# Sheet1.net
KiCad netlist of a schematic drawn in Altium Designer
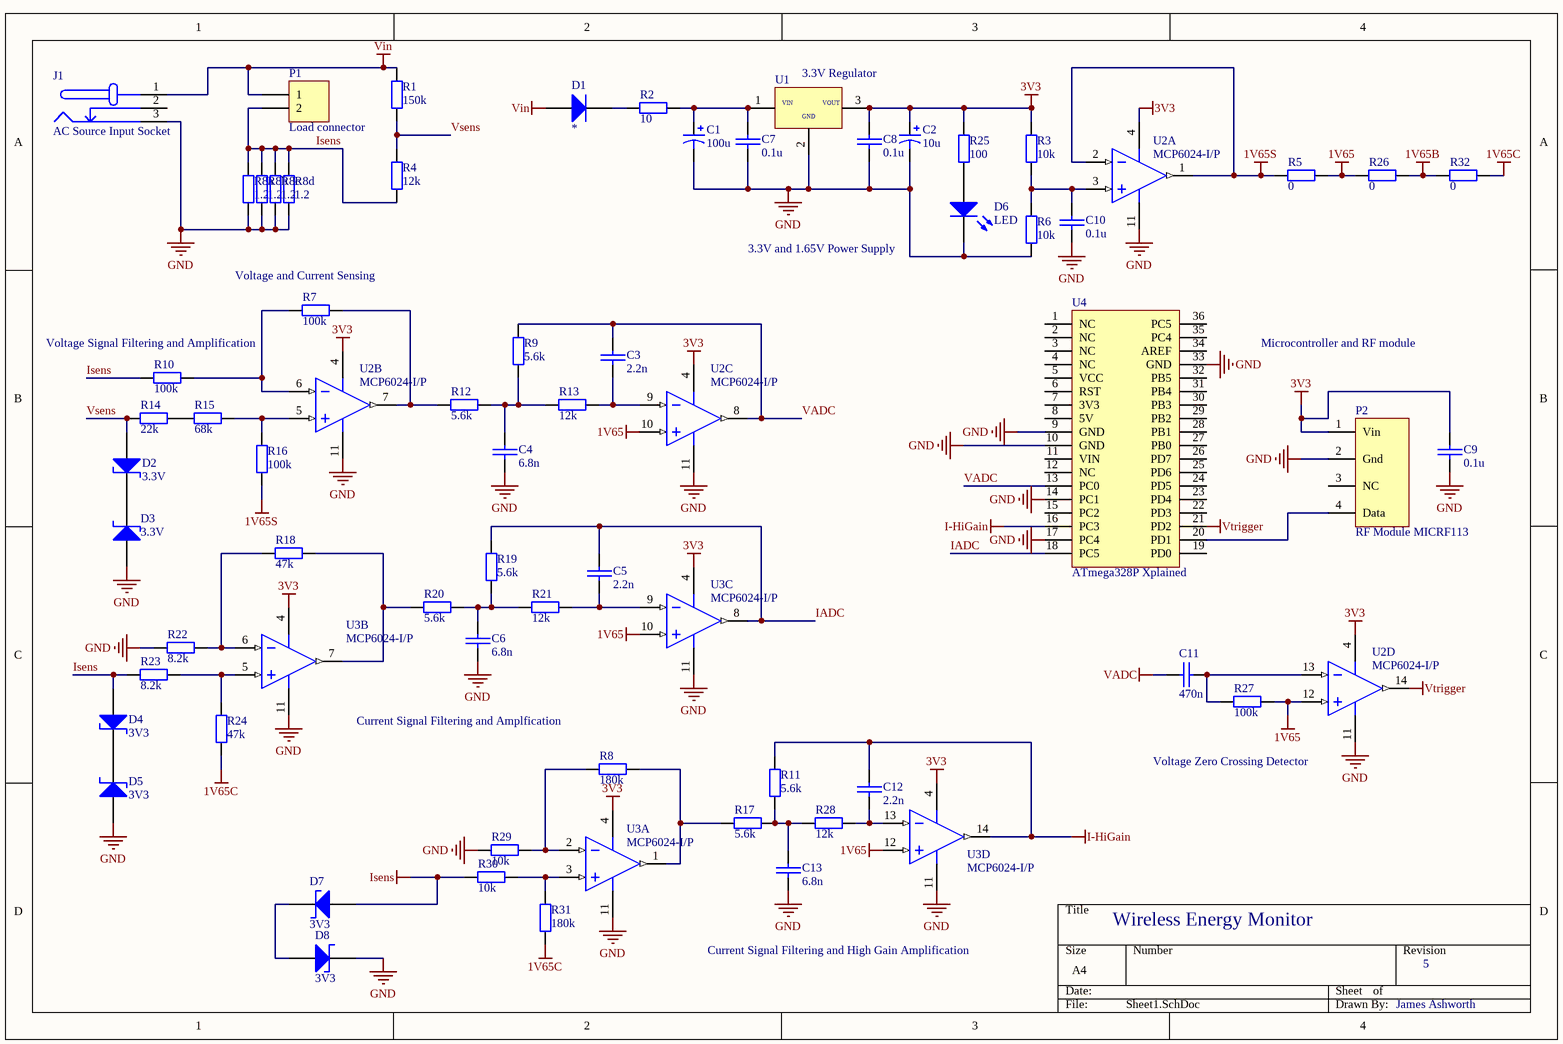
[diagram p0: Sheet1.SchDoc]

(export (version "E")
  (design (tool "Eeschema 10.0.6"))
  (components
    (comp (ref "C1")
      (value "100u")
      (footprint "CAP-RAD-3mm Pitch")
      (description "Polarized Capacitor (Axial)")
      (fields (field (name "PUBLISHER") "Altium Limited"))
      (libsource (lib "EE209_SCHLibrary") (part "Cap Pol (22uF-100uF)"))
    )
    (comp (ref "C2")
      (value "10u")
      (footprint "CAP-RAD-2mm Pitch")
      (description "Polarized Capacitor (Axial)")
      (fields (field (name "PUBLISHER") "Altium Limited"))
      (libsource (lib "EE209_SCHLibrary") (part "Cap Pol (1uF-10uF)"))
    )
    (comp (ref "C3")
      (value "2.2n")
      (footprint "FILM CAP-0.2")
      (description "Capacitor Non Polarised Through Hole")
      (libsource (lib "EE209_SCHLibrary") (part "CAP"))
    )
    (comp (ref "C4")
      (value "6.8n")
      (footprint "FILM CAP-0.2")
      (description "Capacitor Non Polarised Through Hole")
      (libsource (lib "EE209_SCHLibrary") (part "CAP"))
    )
    (comp (ref "C5")
      (value "2.2n")
      (footprint "FILM CAP-0.2")
      (description "Capacitor Non Polarised Through Hole")
      (libsource (lib "EE209_SCHLibrary") (part "CAP"))
    )
    (comp (ref "C6")
      (value "6.8n")
      (footprint "FILM CAP-0.2")
      (description "Capacitor Non Polarised Through Hole")
      (libsource (lib "EE209_SCHLibrary") (part "CAP"))
    )
    (comp (ref "C7")
      (value "0.1u")
      (footprint "ECE-CAPR0.2x0.1TH")
      (description "CAP CER 10pF 50V TH")
      (libsource (lib "EceParts") (part "Cap"))
    )
    (comp (ref "C8")
      (value "0.1u")
      (footprint "ECE-CAPR0.2x0.1TH")
      (description "CAP CER 10pF 50V TH")
      (libsource (lib "EceParts") (part "Cap"))
    )
    (comp (ref "C9")
      (value "0.1u")
      (footprint "FILM CAP-0.2")
      (description "Capacitor Non Polarised Through Hole")
      (libsource (lib "EE209_SCHLibrary") (part "CAP"))
    )
    (comp (ref "C10")
      (value "0.1u")
      (footprint "FILM CAP-0.2")
      (description "Capacitor Non Polarised Through Hole")
      (libsource (lib "EE209_SCHLibrary") (part "CAP"))
    )
    (comp (ref "C11")
      (value "470n")
      (footprint "FILM CAP-0.2")
      (description "Capacitor Non Polarised Through Hole")
      (libsource (lib "EE209_SCHLibrary") (part "CAP"))
    )
    (comp (ref "C12")
      (value "2.2n")
      (footprint "FILM CAP-0.2")
      (description "Capacitor Non Polarised Through Hole")
      (libsource (lib "EE209_SCHLibrary") (part "CAP"))
    )
    (comp (ref "C13")
      (value "6.8n")
      (footprint "FILM CAP-0.2")
      (description "Capacitor Non Polarised Through Hole")
      (libsource (lib "EE209_SCHLibrary") (part "CAP"))
    )
    (comp (ref "D1")
      (value "*")
      (footprint "AXIAL-DIODE-0.4")
      (fields
        (field (name "MANUFACTURER") "Fairchild Semiconductor")
        (field (name "PUBLISHER") "Altium Limited")
      )
      (libsource (lib "EE209_SCHLibrary") (part "Diode"))
    )
    (comp (ref "D2")
      (value "3.3V")
      (footprint "AXIAL-DIODE-0.4")
      (description "Zener Diode")
      (libsource (lib "EE209_SCHLibrary") (part "Zener"))
    )
    (comp (ref "D3")
      (value "3.3V")
      (footprint "AXIAL-DIODE-0.4")
      (description "Zener Diode")
      (libsource (lib "EE209_SCHLibrary") (part "Zener"))
    )
    (comp (ref "D4")
      (value "3V3")
      (footprint "AXIAL-DIODE-0.4")
      (description "Zener Diode")
      (libsource (lib "EE209_SCHLibrary") (part "Zener"))
    )
    (comp (ref "D5")
      (value "3V3")
      (footprint "AXIAL-DIODE-0.4")
      (description "Zener Diode")
      (libsource (lib "EE209_SCHLibrary") (part "Zener"))
    )
    (comp (ref "D6")
      (value "LED")
      (footprint "LED")
      (description "Typical GaAs LED")
      (fields (field (name "MANUFACTURER") "Generic Components") (field (name "PUBLISHER") "Altium Limited"))
      (libsource (lib "EE209_SCHLibrary") (part "LED"))
    )
    (comp (ref "D7")
      (value "3V3")
      (footprint "AXIAL-DIODE-0.4")
      (description "Zener Diode")
      (libsource (lib "EE209_SCHLibrary") (part "Zener"))
    )
    (comp (ref "D8")
      (value "3V3")
      (footprint "AXIAL-DIODE-0.4")
      (description "Zener Diode")
      (libsource (lib "EE209_SCHLibrary") (part "Zener"))
    )
    (comp (ref "J1")
      (value "AC Source Input Socket")
      (footprint "AC-Socket")
      (libsource (lib "EE209_SCHLibrary") (part "AC Input"))
    )
    (comp (ref "P1")
      (value "Load connector")
      (footprint "Dual Banana Plug")
      (description "M6 Holes")
      (fields (field (name "PUBLISHER") "Altium Limited"))
      (libsource (lib "EE209_SCHLibrary") (part "Dual Banana Plugs"))
    )
    (comp (ref "P2")
      (value "RF Module MICRF113")
      (footprint "MICRF113 TX")
      (description "Vertical Mount RF Module")
      (libsource (lib "EE209_SCHLibrary") (part "RF Module"))
    )
    (comp (ref "R1")
      (value "150k")
      (footprint "AXIAL-0.4")
      (description "Through Hole Resistor")
      (fields (field (name "PUBLISHER") "Altium Limited"))
      (libsource (lib "") (part "Res_2"))
    )
    (comp (ref "R2")
      (value "10")
      (footprint "AXIAL-0.4")
      (description "Through Hole Resistor")
      (fields (field (name "PUBLISHER") "Altium Limited"))
      (libsource (lib "EE209_SCHLibrary") (part "Res"))
    )
    (comp (ref "R3")
      (value "10k")
      (footprint "AXIAL-0.4")
      (description "Through Hole Resistor")
      (fields (field (name "PUBLISHER") "Altium Limited"))
      (libsource (lib "") (part "Res_2"))
    )
    (comp (ref "R4")
      (value "12k")
      (footprint "AXIAL-0.4")
      (description "Through Hole Resistor")
      (fields (field (name "PUBLISHER") "Altium Limited"))
      (libsource (lib "") (part "Res_2"))
    )
    (comp (ref "R5")
      (value "0")
      (footprint "AXIAL-0.4")
      (description "Through Hole Resistor")
      (fields (field (name "PUBLISHER") "Altium Limited"))
      (libsource (lib "EE209_SCHLibrary") (part "Res"))
    )
    (comp (ref "R6")
      (value "10k")
      (footprint "AXIAL-0.4")
      (description "Through Hole Resistor")
      (fields (field (name "PUBLISHER") "Altium Limited"))
      (libsource (lib "") (part "Res_2"))
    )
    (comp (ref "R7")
      (value "100k")
      (footprint "AXIAL-0.4")
      (description "Through Hole Resistor")
      (fields (field (name "PUBLISHER") "Altium Limited"))
      (libsource (lib "EE209_SCHLibrary") (part "Res"))
    )
    (comp (ref "R8")
      (value "180k")
      (footprint "AXIAL-0.4")
      (description "Through Hole Resistor")
      (fields (field (name "PUBLISHER") "Altium Limited"))
      (libsource (lib "") (part "Res_1"))
    )
    (comp (ref "R8a")
      (value "1.2")
      (footprint "AXIAL-0.4")
      (description "Through Hole Resistor")
      (fields (field (name "PUBLISHER") "Altium Limited"))
      (libsource (lib "") (part "Res_2"))
    )
    (comp (ref "R8b")
      (value "1.2")
      (footprint "AXIAL-0.4")
      (description "Through Hole Resistor")
      (fields (field (name "PUBLISHER") "Altium Limited"))
      (libsource (lib "") (part "Res_2"))
    )
    (comp (ref "R8c")
      (value "1.2")
      (footprint "AXIAL-0.4")
      (description "Through Hole Resistor")
      (fields (field (name "PUBLISHER") "Altium Limited"))
      (libsource (lib "") (part "Res_2"))
    )
    (comp (ref "R8d")
      (value "1.2")
      (footprint "AXIAL-0.4")
      (description "Through Hole Resistor")
      (fields (field (name "PUBLISHER") "Altium Limited"))
      (libsource (lib "") (part "Res_2"))
    )
    (comp (ref "R9")
      (value "5.6k")
      (footprint "AXIAL-0.4")
      (description "Through Hole Resistor")
      (fields (field (name "PUBLISHER") "Altium Limited"))
      (libsource (lib "") (part "Res_2"))
    )
    (comp (ref "R10")
      (value "100k")
      (footprint "AXIAL-0.4")
      (description "Through Hole Resistor")
      (fields (field (name "PUBLISHER") "Altium Limited"))
      (libsource (lib "EE209_SCHLibrary") (part "Res"))
    )
    (comp (ref "R11")
      (value "5.6k")
      (footprint "AXIAL-0.4")
      (description "Through Hole Resistor")
      (fields (field (name "PUBLISHER") "Altium Limited"))
      (libsource (lib "") (part "Res_3"))
    )
    (comp (ref "R12")
      (value "5.6k")
      (footprint "AXIAL-0.4")
      (description "Through Hole Resistor")
      (fields (field (name "PUBLISHER") "Altium Limited"))
      (libsource (lib "EE209_SCHLibrary") (part "Res"))
    )
    (comp (ref "R13")
      (value "12k")
      (footprint "AXIAL-0.4")
      (description "Through Hole Resistor")
      (fields (field (name "PUBLISHER") "Altium Limited"))
      (libsource (lib "") (part "Res_1"))
    )
    (comp (ref "R14")
      (value "22k")
      (footprint "AXIAL-0.4")
      (description "Through Hole Resistor")
      (fields (field (name "PUBLISHER") "Altium Limited"))
      (libsource (lib "EE209_SCHLibrary") (part "Res"))
    )
    (comp (ref "R15")
      (value "68k")
      (footprint "AXIAL-0.4")
      (description "Through Hole Resistor")
      (fields (field (name "PUBLISHER") "Altium Limited"))
      (libsource (lib "EE209_SCHLibrary") (part "Res"))
    )
    (comp (ref "R16")
      (value "100k")
      (footprint "AXIAL-0.4")
      (description "Through Hole Resistor")
      (fields (field (name "PUBLISHER") "Altium Limited"))
      (libsource (lib "") (part "Res_2"))
    )
    (comp (ref "R17")
      (value "5.6k")
      (footprint "AXIAL-0.4")
      (description "Through Hole Resistor")
      (fields (field (name "PUBLISHER") "Altium Limited"))
      (libsource (lib "") (part "Res_1"))
    )
    (comp (ref "R18")
      (value "47k")
      (footprint "AXIAL-0.4")
      (description "Through Hole Resistor")
      (fields (field (name "PUBLISHER") "Altium Limited"))
      (libsource (lib "") (part "Res_1"))
    )
    (comp (ref "R19")
      (value "5.6k")
      (footprint "AXIAL-0.4")
      (description "Through Hole Resistor")
      (fields (field (name "PUBLISHER") "Altium Limited"))
      (libsource (lib "") (part "Res_3"))
    )
    (comp (ref "R20")
      (value "5.6k")
      (footprint "AXIAL-0.4")
      (description "Through Hole Resistor")
      (fields (field (name "PUBLISHER") "Altium Limited"))
      (libsource (lib "") (part "Res_1"))
    )
    (comp (ref "R21")
      (value "12k")
      (footprint "AXIAL-0.4")
      (description "Through Hole Resistor")
      (fields (field (name "PUBLISHER") "Altium Limited"))
      (libsource (lib "") (part "Res_1"))
    )
    (comp (ref "R22")
      (value "8.2k")
      (footprint "AXIAL-0.4")
      (description "Through Hole Resistor")
      (fields (field (name "PUBLISHER") "Altium Limited"))
      (libsource (lib "EE209_SCHLibrary") (part "Res"))
    )
    (comp (ref "R23")
      (value "8.2k")
      (footprint "AXIAL-0.4")
      (description "Through Hole Resistor")
      (fields (field (name "PUBLISHER") "Altium Limited"))
      (libsource (lib "EE209_SCHLibrary") (part "Res"))
    )
    (comp (ref "R24")
      (value "47k")
      (footprint "AXIAL-0.4")
      (description "Through Hole Resistor")
      (fields (field (name "PUBLISHER") "Altium Limited"))
      (libsource (lib "") (part "Res_2"))
    )
    (comp (ref "R25")
      (value "100")
      (footprint "AXIAL-0.4")
      (description "Through Hole Resistor")
      (fields (field (name "PUBLISHER") "Altium Limited"))
      (libsource (lib "") (part "Res_2"))
    )
    (comp (ref "R26")
      (value "0")
      (footprint "AXIAL-0.4")
      (description "Through Hole Resistor")
      (fields (field (name "PUBLISHER") "Altium Limited"))
      (libsource (lib "EE209_SCHLibrary") (part "Res"))
    )
    (comp (ref "R27")
      (value "100k")
      (footprint "AXIAL-0.4")
      (description "Through Hole Resistor")
      (fields (field (name "PUBLISHER") "Altium Limited"))
      (libsource (lib "EE209_SCHLibrary") (part "Res"))
    )
    (comp (ref "R28")
      (value "12k")
      (footprint "AXIAL-0.4")
      (description "Through Hole Resistor")
      (fields (field (name "PUBLISHER") "Altium Limited"))
      (libsource (lib "") (part "Res_1"))
    )
    (comp (ref "R29")
      (value "10k")
      (footprint "AXIAL-0.4")
      (description "Through Hole Resistor")
      (fields (field (name "PUBLISHER") "Altium Limited"))
      (libsource (lib "") (part "Res_1"))
    )
    (comp (ref "R30")
      (value "10k")
      (footprint "AXIAL-0.4")
      (description "Through Hole Resistor")
      (fields (field (name "PUBLISHER") "Altium Limited"))
      (libsource (lib "EE209_SCHLibrary") (part "Res"))
    )
    (comp (ref "R31")
      (value "180k")
      (footprint "AXIAL-0.4")
      (description "Through Hole Resistor")
      (fields (field (name "PUBLISHER") "Altium Limited"))
      (libsource (lib "") (part "Res_2"))
    )
    (comp (ref "R32")
      (value "0")
      (footprint "AXIAL-0.4")
      (description "Through Hole Resistor")
      (fields (field (name "PUBLISHER") "Altium Limited"))
      (libsource (lib "EE209_SCHLibrary") (part "Res"))
    )
    (comp (ref "U1")
      (value "3.3V Regulator")
      (footprint "TO-92")
      (libsource (lib "EE209_SCHLibrary") (part "LP2950-33"))
    )
    (comp (ref "U2")
      (value "MCP6024-I/P")
      (footprint "DIP-14")
      (description "Rail-to-Rail Input/Output, 10 MHz Operational Amplifier, 14-Pin PDIP, Industrial Temperature")
      (fields (field (name "PUBLISHER") "Altium Limited"))
      (libsource (lib "EE209_SCHLibrary") (part "MCP6024-I/P"))
    )
    (comp (ref "U3")
      (value "MCP6024-I/P")
      (footprint "DIP-14")
      (description "Rail-to-Rail Input/Output, 10 MHz Operational Amplifier, 14-Pin PDIP, Industrial Temperature")
      (fields (field (name "PUBLISHER") "Altium Limited"))
      (libsource (lib "EE209_SCHLibrary") (part "MCP6024-I/P"))
    )
    (comp (ref "U4")
      (value "ATmega328P Xplained")
      (footprint "ATmeg328P Xplained")
      (description "Header, 18-Pin, Dual row")
      (fields (field (name "PUBLISHER") "Altium Limited"))
      (libsource (lib "EE209_SCHLibrary") (part "ATmega328P Xplained"))
    )
  )
  (nets
    (net (code "1") (name "/IADC") (class "Default")
      (node (ref "C5") (pin "1") (pinfunction "1_1") (pintype "passive"))
      (node (ref "R19") (pin "1") (pinfunction "1_1") (pintype "passive"))
      (node (ref "U3") (pin "8") (pinfunction "VOUTC_8") (pintype "output"))
      (node (ref "U4") (pin "18") (pinfunction "PC5_18") (pintype "passive"))
    )
    (net (code "2") (name "/Vsens") (class "Default")
      (node (ref "D2") (pin "1") (pinfunction "A_1") (pintype "passive"))
      (node (ref "R1") (pin "1") (pinfunction "1_1") (pintype "passive"))
      (node (ref "R14") (pin "1") (pinfunction "1_1") (pintype "passive"))
      (node (ref "R4") (pin "2") (pinfunction "2_2") (pintype "passive"))
    )
    (net (code "3") (name "1V65") (class "Default")
      (node (ref "R26") (pin "1") (pinfunction "1_1") (pintype "passive"))
      (node (ref "R27") (pin "2") (pinfunction "2_2") (pintype "passive"))
      (node (ref "R5") (pin "2") (pinfunction "2_2") (pintype "passive"))
      (node (ref "U2") (pin "10") (pinfunction "VINC+_10") (pintype "input"))
      (node (ref "U2") (pin "12") (pinfunction "VIND+_12") (pintype "input"))
      (node (ref "U3") (pin "10") (pinfunction "VINC+_10") (pintype "input"))
      (node (ref "U3") (pin "12") (pinfunction "VIND+_12") (pintype "input"))
    )
    (net (code "4") (name "1V65B") (class "Default")
      (node (ref "R26") (pin "2") (pinfunction "2_2") (pintype "passive"))
      (node (ref "R32") (pin "1") (pinfunction "1_1") (pintype "passive"))
    )
    (net (code "5") (name "1V65C") (class "Default")
      (node (ref "R24") (pin "1") (pinfunction "1_1") (pintype "passive"))
      (node (ref "R31") (pin "1") (pinfunction "1_1") (pintype "passive"))
      (node (ref "R32") (pin "2") (pinfunction "2_2") (pintype "passive"))
    )
    (net (code "6") (name "1V65S") (class "Default")
      (node (ref "R16") (pin "1") (pinfunction "1_1") (pintype "passive"))
      (node (ref "R5") (pin "1") (pinfunction "1_1") (pintype "passive"))
      (node (ref "U2") (pin "1") (pinfunction "VOUTA_1") (pintype "output"))
      (node (ref "U2") (pin "2") (pinfunction "VINA-_2") (pintype "input"))
    )
    (net (code "7") (name "3V3") (class "Default")
      (node (ref "C2") (pin "1") (pinfunction "1_1") (pintype "passive"))
      (node (ref "C8") (pin "1") (pinfunction "1_1") (pintype "passive"))
      (node (ref "C9") (pin "1") (pinfunction "1_1") (pintype "passive"))
      (node (ref "P2") (pin "1") (pinfunction "Vin_1") (pintype "passive"))
      (node (ref "R25") (pin "2") (pinfunction "2_2") (pintype "passive"))
      (node (ref "R3") (pin "2") (pinfunction "2_2") (pintype "passive"))
      (node (ref "U1") (pin "3") (pinfunction "OUTPUT_3") (pintype "passive"))
      (node (ref "U2") (pin "4") (pinfunction "VDD_4") (pintype "power_in"))
      (node (ref "U3") (pin "4") (pinfunction "VDD_4") (pintype "power_in"))
    )
    (net (code "8") (name "GND") (class "Default")
      (node (ref "C1") (pin "2") (pinfunction "2_2") (pintype "passive"))
      (node (ref "C10") (pin "2") (pinfunction "2_2") (pintype "passive"))
      (node (ref "C13") (pin "2") (pinfunction "2_2") (pintype "passive"))
      (node (ref "C2") (pin "2") (pinfunction "2_2") (pintype "passive"))
      (node (ref "C4") (pin "2") (pinfunction "2_2") (pintype "passive"))
      (node (ref "C6") (pin "2") (pinfunction "2_2") (pintype "passive"))
      (node (ref "C7") (pin "2") (pinfunction "2_2") (pintype "passive"))
      (node (ref "C8") (pin "2") (pinfunction "2_2") (pintype "passive"))
      (node (ref "C9") (pin "2") (pinfunction "2_2") (pintype "passive"))
      (node (ref "D3") (pin "1") (pinfunction "A_1") (pintype "passive"))
      (node (ref "D5") (pin "1") (pinfunction "A_1") (pintype "passive"))
      (node (ref "D6") (pin "2") (pinfunction "K_2") (pintype "passive"))
      (node (ref "D8") (pin "2") (pinfunction "K_2") (pintype "passive"))
      (node (ref "J1") (pin "3") (pinfunction "GND_3") (pintype "power_in"))
      (node (ref "P2") (pin "2") (pinfunction "Gnd_2") (pintype "passive"))
      (node (ref "R22") (pin "1") (pinfunction "1_1") (pintype "passive"))
      (node (ref "R29") (pin "2") (pinfunction "2_2") (pintype "passive"))
      (node (ref "R6") (pin "1") (pinfunction "1_1") (pintype "passive"))
      (node (ref "R8a") (pin "1") (pinfunction "1_1") (pintype "passive"))
      (node (ref "R8b") (pin "1") (pinfunction "1_1") (pintype "passive"))
      (node (ref "R8c") (pin "1") (pinfunction "1_1") (pintype "passive"))
      (node (ref "R8d") (pin "1") (pinfunction "1_1") (pintype "passive"))
      (node (ref "U1") (pin "2") (pinfunction "GND_2") (pintype "passive"))
      (node (ref "U2") (pin "11") (pinfunction "VSS_11") (pintype "power_in"))
      (node (ref "U3") (pin "11") (pinfunction "VSS_11") (pintype "power_in"))
      (node (ref "U4") (pin "10") (pinfunction "GND_10") (pintype "power_in"))
      (node (ref "U4") (pin "14") (pinfunction "PC1_14") (pintype "passive"))
      (node (ref "U4") (pin "17") (pinfunction "PC4_17") (pintype "passive"))
      (node (ref "U4") (pin "33") (pinfunction "GND_33") (pintype "passive"))
      (node (ref "U4") (pin "9") (pinfunction "GND_9") (pintype "power_in"))
    )
    (net (code "9") (name "I-HiGain") (class "Default")
      (node (ref "C12") (pin "1") (pinfunction "1_1") (pintype "passive"))
      (node (ref "R11") (pin "1") (pinfunction "1_1") (pintype "passive"))
      (node (ref "U3") (pin "14") (pinfunction "VOUTD_14") (pintype "output"))
      (node (ref "U4") (pin "16") (pinfunction "PC3_16") (pintype "passive"))
    )
    (net (code "10") (name "Isens") (class "Default")
      (node (ref "D4") (pin "1") (pinfunction "A_1") (pintype "passive"))
      (node (ref "D7") (pin "1") (pinfunction "A_1") (pintype "passive"))
      (node (ref "P1") (pin "2") (pinfunction "2_2") (pintype "passive"))
      (node (ref "R10") (pin "1") (pinfunction "1_1") (pintype "passive"))
      (node (ref "R23") (pin "1") (pinfunction "1_1") (pintype "passive"))
      (node (ref "R30") (pin "1") (pinfunction "1_1") (pintype "passive"))
      (node (ref "R4") (pin "1") (pinfunction "1_1") (pintype "passive"))
      (node (ref "R8a") (pin "2") (pinfunction "2_2") (pintype "passive"))
      (node (ref "R8b") (pin "2") (pinfunction "2_2") (pintype "passive"))
      (node (ref "R8c") (pin "2") (pinfunction "2_2") (pintype "passive"))
      (node (ref "R8d") (pin "2") (pinfunction "2_2") (pintype "passive"))
    )
    (net (code "11") (name "Net-(C4-Pad1)") (class "Default")
      (node (ref "C4") (pin "1") (pinfunction "1_1") (pintype "passive"))
      (node (ref "R12") (pin "2") (pinfunction "2_2") (pintype "passive"))
      (node (ref "R13") (pin "2") (pinfunction "2_2") (pintype "passive"))
      (node (ref "R9") (pin "1") (pinfunction "1_1") (pintype "passive"))
    )
    (net (code "12") (name "Net-(C6-Pad1)") (class "Default")
      (node (ref "C6") (pin "1") (pinfunction "1_1") (pintype "passive"))
      (node (ref "R19") (pin "2") (pinfunction "2_2") (pintype "passive"))
      (node (ref "R20") (pin "1") (pinfunction "1_1") (pintype "passive"))
      (node (ref "R21") (pin "2") (pinfunction "2_2") (pintype "passive"))
    )
    (net (code "13") (name "Net-(C13-Pad1)") (class "Default")
      (node (ref "C13") (pin "1") (pinfunction "1_1") (pintype "passive"))
      (node (ref "R11") (pin "2") (pinfunction "2_2") (pintype "passive"))
      (node (ref "R17") (pin "1") (pinfunction "1_1") (pintype "passive"))
      (node (ref "R28") (pin "2") (pinfunction "2_2") (pintype "passive"))
    )
    (net (code "14") (name "Net-(D1-K)") (class "Default")
      (node (ref "D1") (pin "2") (pinfunction "K_2") (pintype "passive"))
      (node (ref "R2") (pin "1") (pinfunction "1_1") (pintype "passive"))
    )
    (net (code "15") (name "Net-(D2-K)") (class "Default")
      (node (ref "D2") (pin "2") (pinfunction "K_2") (pintype "passive"))
      (node (ref "D3") (pin "2") (pinfunction "K_2") (pintype "passive"))
    )
    (net (code "16") (name "Net-(D4-K)") (class "Default")
      (node (ref "D4") (pin "2") (pinfunction "K_2") (pintype "passive"))
      (node (ref "D5") (pin "2") (pinfunction "K_2") (pintype "passive"))
    )
    (net (code "17") (name "Net-(D6-A)") (class "Default")
      (node (ref "D6") (pin "1") (pinfunction "A_1") (pintype "passive"))
      (node (ref "R25") (pin "1") (pinfunction "1_1") (pintype "passive"))
    )
    (net (code "18") (name "Net-(D7-K)") (class "Default")
      (node (ref "D7") (pin "2") (pinfunction "K_2") (pintype "passive"))
      (node (ref "D8") (pin "1") (pinfunction "A_1") (pintype "passive"))
    )
    (net (code "19") (name "Net-(P2-Data)") (class "Default")
      (node (ref "P2") (pin "4") (pinfunction "Data_4") (pintype "passive"))
      (node (ref "U4") (pin "20") (pinfunction "PD1_20") (pintype "passive"))
    )
    (net (code "20") (name "Net-(R14-Pad2)") (class "Default")
      (node (ref "R14") (pin "2") (pinfunction "2_2") (pintype "passive"))
      (node (ref "R15") (pin "1") (pinfunction "1_1") (pintype "passive"))
    )
    (net (code "21") (name "Net-(U1-INPUT)") (class "Default")
      (node (ref "C1") (pin "1") (pinfunction "1_1") (pintype "passive"))
      (node (ref "C7") (pin "1") (pinfunction "1_1") (pintype "passive"))
      (node (ref "R2") (pin "2") (pinfunction "2_2") (pintype "passive"))
      (node (ref "U1") (pin "1") (pinfunction "INPUT_1") (pintype "passive"))
    )
    (net (code "22") (name "Net-(U2A-VINA+)") (class "Default")
      (node (ref "C10") (pin "1") (pinfunction "1_1") (pintype "passive"))
      (node (ref "R3") (pin "1") (pinfunction "1_1") (pintype "passive"))
      (node (ref "R6") (pin "2") (pinfunction "2_2") (pintype "passive"))
      (node (ref "U2") (pin "3") (pinfunction "VINA+_3") (pintype "input"))
    )
    (net (code "23") (name "Net-(U2B-VINB+)") (class "Default")
      (node (ref "R15") (pin "2") (pinfunction "2_2") (pintype "passive"))
      (node (ref "R16") (pin "2") (pinfunction "2_2") (pintype "passive"))
      (node (ref "U2") (pin "5") (pinfunction "VINB+_5") (pintype "input"))
    )
    (net (code "24") (name "Net-(U2B-VINB-)") (class "Default")
      (node (ref "R10") (pin "2") (pinfunction "2_2") (pintype "passive"))
      (node (ref "R7") (pin "1") (pinfunction "1_1") (pintype "passive"))
      (node (ref "U2") (pin "6") (pinfunction "VINB-_6") (pintype "input"))
    )
    (net (code "25") (name "Net-(U2B-VOUTB)") (class "Default")
      (node (ref "R12") (pin "1") (pinfunction "1_1") (pintype "passive"))
      (node (ref "R7") (pin "2") (pinfunction "2_2") (pintype "passive"))
      (node (ref "U2") (pin "7") (pinfunction "VOUTB_7") (pintype "output"))
    )
    (net (code "26") (name "Net-(U2C-VINC-)") (class "Default")
      (node (ref "C3") (pin "2") (pinfunction "2_2") (pintype "passive"))
      (node (ref "R13") (pin "1") (pinfunction "1_1") (pintype "passive"))
      (node (ref "U2") (pin "9") (pinfunction "VINC-_9") (pintype "input"))
    )
    (net (code "27") (name "Net-(U2D-VIND-)") (class "Default")
      (node (ref "C11") (pin "1") (pinfunction "1_1") (pintype "passive"))
      (node (ref "R27") (pin "1") (pinfunction "1_1") (pintype "passive"))
      (node (ref "U2") (pin "13") (pinfunction "VIND-_13") (pintype "input"))
    )
    (net (code "28") (name "Net-(U3A-VINA+)") (class "Default")
      (node (ref "R30") (pin "2") (pinfunction "2_2") (pintype "passive"))
      (node (ref "R31") (pin "2") (pinfunction "2_2") (pintype "passive"))
      (node (ref "U3") (pin "3") (pinfunction "VINA+_3") (pintype "input"))
    )
    (net (code "29") (name "Net-(U3A-VINA-)") (class "Default")
      (node (ref "R29") (pin "1") (pinfunction "1_1") (pintype "passive"))
      (node (ref "R8") (pin "2") (pinfunction "2_2") (pintype "passive"))
      (node (ref "U3") (pin "2") (pinfunction "VINA-_2") (pintype "input"))
    )
    (net (code "30") (name "Net-(U3A-VOUTA)") (class "Default")
      (node (ref "R17") (pin "2") (pinfunction "2_2") (pintype "passive"))
      (node (ref "R8") (pin "1") (pinfunction "1_1") (pintype "passive"))
      (node (ref "U3") (pin "1") (pinfunction "VOUTA_1") (pintype "output"))
    )
    (net (code "31") (name "Net-(U3B-VINB+)") (class "Default")
      (node (ref "R23") (pin "2") (pinfunction "2_2") (pintype "passive"))
      (node (ref "R24") (pin "2") (pinfunction "2_2") (pintype "passive"))
      (node (ref "U3") (pin "5") (pinfunction "VINB+_5") (pintype "input"))
    )
    (net (code "32") (name "Net-(U3B-VINB-)") (class "Default")
      (node (ref "R18") (pin "2") (pinfunction "2_2") (pintype "passive"))
      (node (ref "R22") (pin "2") (pinfunction "2_2") (pintype "passive"))
      (node (ref "U3") (pin "6") (pinfunction "VINB-_6") (pintype "input"))
    )
    (net (code "33") (name "Net-(U3B-VOUTB)") (class "Default")
      (node (ref "R18") (pin "1") (pinfunction "1_1") (pintype "passive"))
      (node (ref "R20") (pin "2") (pinfunction "2_2") (pintype "passive"))
      (node (ref "U3") (pin "7") (pinfunction "VOUTB_7") (pintype "output"))
    )
    (net (code "34") (name "Net-(U3C-VINC-)") (class "Default")
      (node (ref "C5") (pin "2") (pinfunction "2_2") (pintype "passive"))
      (node (ref "R21") (pin "1") (pinfunction "1_1") (pintype "passive"))
      (node (ref "U3") (pin "9") (pinfunction "VINC-_9") (pintype "input"))
    )
    (net (code "35") (name "Net-(U3D-VIND-)") (class "Default")
      (node (ref "C12") (pin "2") (pinfunction "2_2") (pintype "passive"))
      (node (ref "R28") (pin "1") (pinfunction "1_1") (pintype "passive"))
      (node (ref "U3") (pin "13") (pinfunction "VIND-_13") (pintype "input"))
    )
    (net (code "36") (name "VADC") (class "Default")
      (node (ref "C11") (pin "2") (pinfunction "2_2") (pintype "passive"))
      (node (ref "C3") (pin "1") (pinfunction "1_1") (pintype "passive"))
      (node (ref "R9") (pin "2") (pinfunction "2_2") (pintype "passive"))
      (node (ref "U2") (pin "8") (pinfunction "VOUTC_8") (pintype "output"))
      (node (ref "U4") (pin "13") (pinfunction "PC0_13") (pintype "passive"))
    )
    (net (code "37") (name "Vin") (class "Default")
      (node (ref "D1") (pin "1") (pinfunction "A_1") (pintype "passive"))
      (node (ref "J1") (pin "1") (pinfunction "VCC_1") (pintype "power_in"))
      (node (ref "P1") (pin "1") (pinfunction "1_1") (pintype "passive"))
      (node (ref "R1") (pin "2") (pinfunction "2_2") (pintype "passive"))
    )
    (net (code "38") (name "Vtrigger") (class "Default")
      (node (ref "U2") (pin "14") (pinfunction "VOUTD_14") (pintype "output"))
      (node (ref "U4") (pin "21") (pinfunction "PD2_21") (pintype "passive"))
    )
    (net (code "39") (name "unconnected-(J1-GND_ALT-Pad2)") (class "Default")
      (node (ref "J1") (pin "2") (pinfunction "GND_ALT_2") (pintype "power_in"))
    )
    (net (code "40") (name "unconnected-(P2-NC-Pad3)") (class "Default")
      (node (ref "P2") (pin "3") (pinfunction "NC_3") (pintype "passive"))
    )
    (net (code "41") (name "unconnected-(U4-3V3-Pad7)") (class "Default")
      (node (ref "U4") (pin "7") (pinfunction "3V3_7") (pintype "passive"))
    )
    (net (code "42") (name "unconnected-(U4-5V-Pad8)") (class "Default")
      (node (ref "U4") (pin "8") (pinfunction "5V_8") (pintype "power_in"))
    )
    (net (code "43") (name "unconnected-(U4-AREF-Pad34)") (class "Default")
      (node (ref "U4") (pin "34") (pinfunction "AREF_34") (pintype "passive"))
    )
    (net (code "44") (name "unconnected-(U4-NC-Pad1)") (class "Default")
      (node (ref "U4") (pin "1") (pinfunction "NC_1") (pintype "passive"))
    )
    (net (code "45") (name "unconnected-(U4-NC-Pad2)") (class "Default")
      (node (ref "U4") (pin "2") (pinfunction "NC_2") (pintype "passive"))
    )
    (net (code "46") (name "unconnected-(U4-NC-Pad3)") (class "Default")
      (node (ref "U4") (pin "3") (pinfunction "NC_3") (pintype "passive"))
    )
    (net (code "47") (name "unconnected-(U4-NC-Pad4)") (class "Default")
      (node (ref "U4") (pin "4") (pinfunction "NC_4") (pintype "passive"))
    )
    (net (code "48") (name "unconnected-(U4-NC-Pad12)") (class "Default")
      (node (ref "U4") (pin "12") (pinfunction "NC_12") (pintype "passive"))
    )
    (net (code "49") (name "unconnected-(U4-PB0-Pad27)") (class "Default")
      (node (ref "U4") (pin "27") (pinfunction "PB0_27") (pintype "passive"))
    )
    (net (code "50") (name "unconnected-(U4-PB1-Pad28)") (class "Default")
      (node (ref "U4") (pin "28") (pinfunction "PB1_28") (pintype "passive"))
    )
    (net (code "51") (name "unconnected-(U4-PB2-Pad29)") (class "Default")
      (node (ref "U4") (pin "29") (pinfunction "PB2_29") (pintype "passive"))
    )
    (net (code "52") (name "unconnected-(U4-PB3-Pad30)") (class "Default")
      (node (ref "U4") (pin "30") (pinfunction "PB3_30") (pintype "passive"))
    )
    (net (code "53") (name "unconnected-(U4-PB4-Pad31)") (class "Default")
      (node (ref "U4") (pin "31") (pinfunction "PB4_31") (pintype "passive"))
    )
    (net (code "54") (name "unconnected-(U4-PB5-Pad32)") (class "Default")
      (node (ref "U4") (pin "32") (pinfunction "PB5_32") (pintype "passive"))
    )
    (net (code "55") (name "unconnected-(U4-PC2-Pad15)") (class "Default")
      (node (ref "U4") (pin "15") (pinfunction "PC2_15") (pintype "passive"))
    )
    (net (code "56") (name "unconnected-(U4-PC4-Pad35)") (class "Default")
      (node (ref "U4") (pin "35") (pinfunction "PC4_35") (pintype "passive"))
    )
    (net (code "57") (name "unconnected-(U4-PC5-Pad36)") (class "Default")
      (node (ref "U4") (pin "36") (pinfunction "PC5_36") (pintype "passive"))
    )
    (net (code "58") (name "unconnected-(U4-PD0-Pad19)") (class "Default")
      (node (ref "U4") (pin "19") (pinfunction "PD0_19") (pintype "passive"))
    )
    (net (code "59") (name "unconnected-(U4-PD3-Pad22)") (class "Default")
      (node (ref "U4") (pin "22") (pinfunction "PD3_22") (pintype "passive"))
    )
    (net (code "60") (name "unconnected-(U4-PD4-Pad23)") (class "Default")
      (node (ref "U4") (pin "23") (pinfunction "PD4_23") (pintype "passive"))
    )
    (net (code "61") (name "unconnected-(U4-PD5-Pad24)") (class "Default")
      (node (ref "U4") (pin "24") (pinfunction "PD5_24") (pintype "passive"))
    )
    (net (code "62") (name "unconnected-(U4-PD6-Pad25)") (class "Default")
      (node (ref "U4") (pin "25") (pinfunction "PD6_25") (pintype "passive"))
    )
    (net (code "63") (name "unconnected-(U4-PD7-Pad26)") (class "Default")
      (node (ref "U4") (pin "26") (pinfunction "PD7_26") (pintype "passive"))
    )
    (net (code "64") (name "unconnected-(U4-RST-Pad6)") (class "Default")
      (node (ref "U4") (pin "6") (pinfunction "RST_6") (pintype "passive"))
    )
    (net (code "65") (name "unconnected-(U4-VCC-Pad5)") (class "Default")
      (node (ref "U4") (pin "5") (pinfunction "VCC_5") (pintype "power_in"))
    )
    (net (code "66") (name "unconnected-(U4-VIN-Pad11)") (class "Default")
      (node (ref "U4") (pin "11") (pinfunction "VIN_11") (pintype "power_in"))
    )
  )
)
